# ECG_Main.net
KiCad netlist of a schematic drawn in Altium Designer
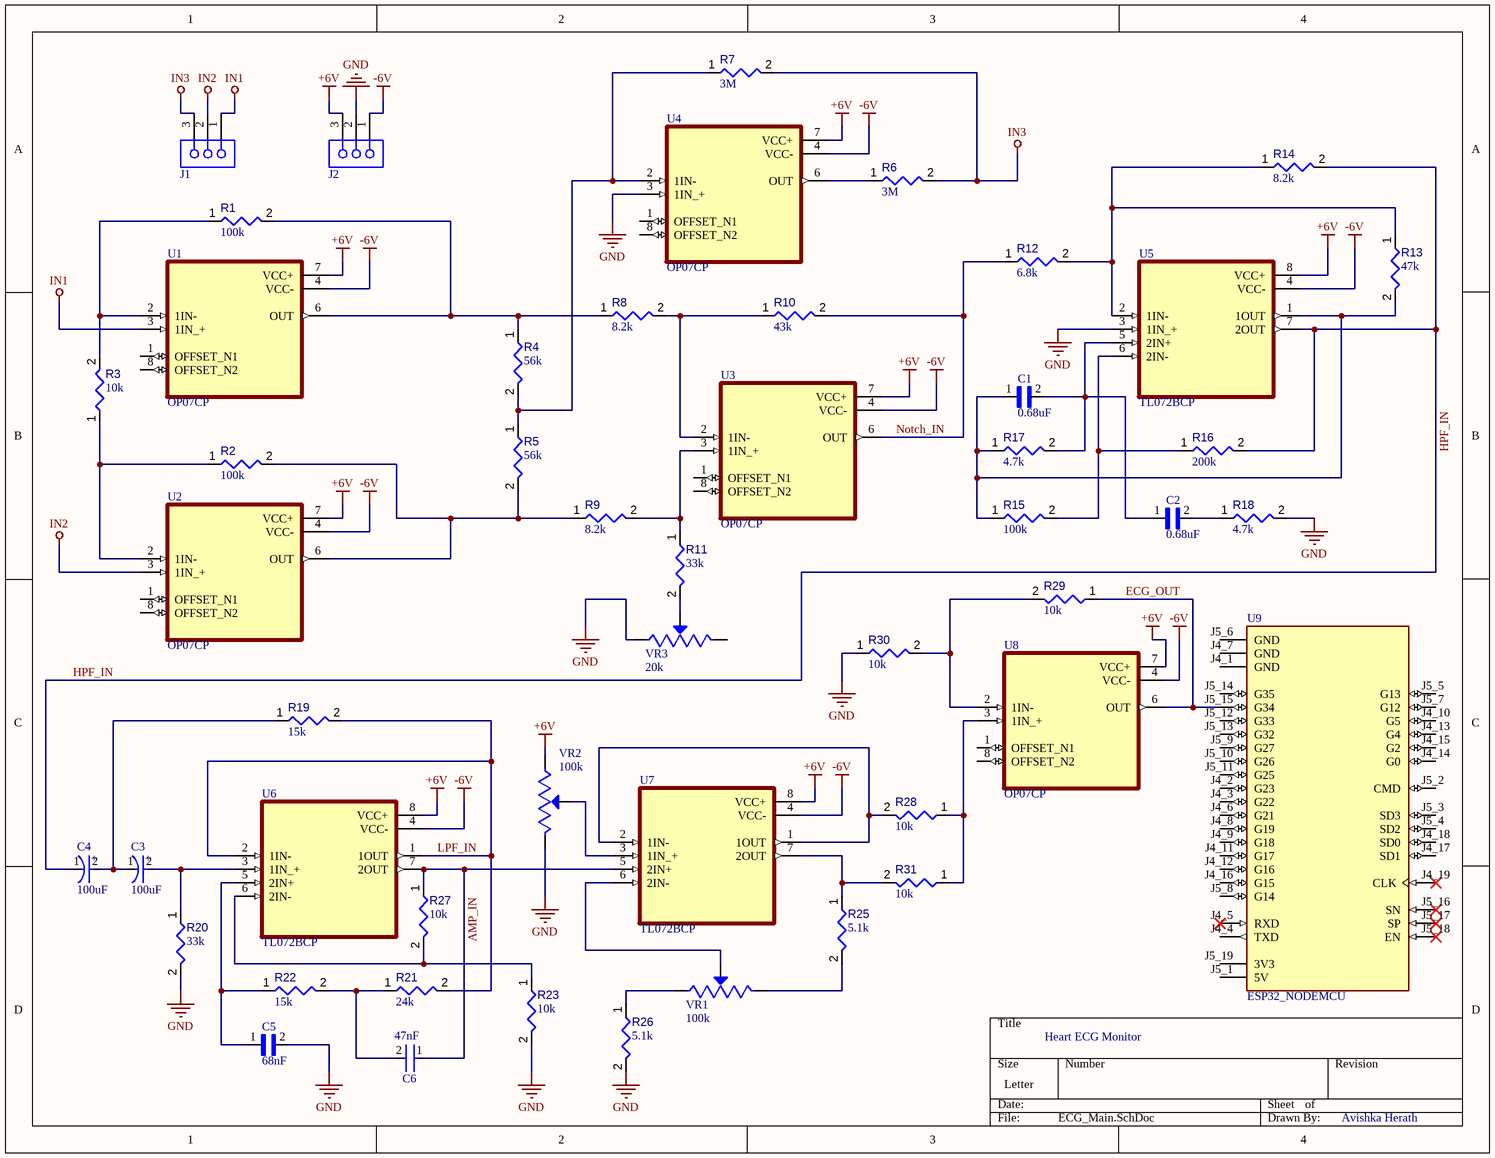
[diagram p0: ECG_Main.SchDoc]

(export (version "E")
  (design (tool "Eeschema 10.0.6"))
  (components
    (comp (ref "C1")
      (value "0.68uF")
      (footprint "CAPRB500W50L550T350H600")
      (fields (field (name "MP") "FA26NP02J472JNU06") (field (name "MF") "{'manufacturer': u'TDK'}"))
      (libsource (lib "SnapEDA_Library") (part "FA26NP02J472JNU06"))
    )
    (comp (ref "C2")
      (value "0.68uF")
      (footprint "CAPRB500W50L550T350H600")
      (fields (field (name "MP") "FA26NP02J472JNU06") (field (name "MF") "{'manufacturer': u'TDK'}"))
      (libsource (lib "SnapEDA_Library") (part "FA26NP02J472JNU06"))
    )
    (comp (ref "C3")
      (value "100uF")
      (footprint "FP-RAD-TH-D_6_3_0_5-L_11-MFG")
      (description "Cap Aluminum Lytic 100uF 25V 20% (6.3 X 11.2mm) Radial 2.5mm 130mA 1000h 105°C Ammo Pack")
      (libsource (lib "University of Moratuwa") (part "203bc49f2ac43e59fd269a8c329ed05"))
    )
    (comp (ref "C4")
      (value "100uF")
      (footprint "FP-RAD-TH-D_6_3_0_5-L_11-MFG")
      (description "Cap Aluminum Lytic 100uF 25V 20% (6.3 X 11.2mm) Radial 2.5mm 130mA 1000h 105°C Ammo Pack")
      (libsource (lib "University of Moratuwa") (part "203bc49f2ac43e59fd269a8c329ed05"))
    )
    (comp (ref "C5")
      (value "68nF")
      (footprint "CAPRR750W60L1030T450H750")
      (fields (field (name "MP") "ECQE2683JF") (field (name "MF") "{'manufacturer': u'Panasonic'}"))
      (libsource (lib "SnapEDA_Library") (part "ECQE2683JF"))
    )
    (comp (ref "C6")
      (value "47nF")
      (footprint "FP-RCE0DB-MFG")
      (description "Cap Ceramic 470pF 50V C0G 5% Radial 2.5mm 125°C Ammo Pack")
      (libsource (lib "University of Moratuwa") (part "b4654b650e69147ec39a6b967a45e02"))
    )
    (comp (ref "J1")
      (value "SIGNAL_IN")
      (footprint "SMTC-SLW-103-01-X-S")
      (fields (field (name "MANUFACTURER") "Samtec") (field (name "PARTNUMBER") "SLW-103-01-G-S"))
      (libsource (lib "Altium Content Vault") (part "SMTC-SLW-103-01-X-S"))
    )
    (comp (ref "J2")
      (value "POWER_IN")
      (footprint "SMTC-SLW-103-01-X-S")
      (fields (field (name "MANUFACTURER") "Samtec") (field (name "PARTNUMBER") "SLW-103-01-G-S"))
      (libsource (lib "Altium Content Vault") (part "SMTC-SLW-103-01-X-S"))
    )
    (comp (ref "R1")
      (value "100k")
      (footprint "RESA60-630X240")
      (description "Axial Resistor, 100 KOhm, +/- 1%, 0.25 W, -55 to 155 degC, 2-Pin THD, RoHS, Bulk")
      (fields (field (name "POWER") "250mW") (field (name "MANUFACTURER") "Yageo"))
      (libsource (lib "University of Moratuwa") (part "RES-2"))
    )
    (comp (ref "R2")
      (value "100k")
      (footprint "RESA60-630X240")
      (description "Axial Resistor, 100 KOhm, +/- 1%, 0.25 W, -55 to 155 degC, 2-Pin THD, RoHS, Bulk")
      (fields (field (name "POWER") "250mW") (field (name "MANUFACTURER") "Yageo"))
      (libsource (lib "University of Moratuwa") (part "RES-2"))
    )
    (comp (ref "R3")
      (value "10k")
      (footprint "RESA60-630X240")
      (description "Axial Resistor, 10 KOhm, +/- 1%, 0.25 W, -55 to 155 degC, 2-Pin THD, RoHS, Bulk")
      (fields (field (name "TOLERANCE") "1%") (field (name "POWER") "250mW"))
      (libsource (lib "University of Moratuwa") (part "RES-2"))
    )
    (comp (ref "R4")
      (value "56k")
      (footprint "RESA60-630X240")
      (description "Axial Resistor, 47.5 KOhm, +/- 1%, 0.25 W, -55 to 155 degC, 2-Pin THD, RoHS, Bulk")
      (fields (field (name "MANUFACTURER") "Yageo") (field (name "TOLERANCE") "1%"))
      (libsource (lib "University of Moratuwa") (part "RES-2"))
    )
    (comp (ref "R5")
      (value "56k")
      (footprint "RESA60-630X240")
      (description "Axial Resistor, 47.5 KOhm, +/- 1%, 0.25 W, -55 to 155 degC, 2-Pin THD, RoHS, Bulk")
      (fields (field (name "MANUFACTURER") "Yageo") (field (name "TOLERANCE") "1%"))
      (libsource (lib "University of Moratuwa") (part "RES-2"))
    )
    (comp (ref "R6")
      (value "3M")
      (footprint "RESA60-630X240")
      (description "Axial Resistor, 1 MOhm, +/- 1%, 250 mW, -55 to 155 degC, 2-Pin THD, RoHS, Bulk")
      (fields (field (name "MANUFACTURER") "Yageo") (field (name "TOLERANCE") "1%"))
      (libsource (lib "University of Moratuwa") (part "RES-2"))
    )
    (comp (ref "R7")
      (value "3M")
      (footprint "RESA60-630X240")
      (description "Axial Resistor, 1 MOhm, +/- 1%, 250 mW, -55 to 155 degC, 2-Pin THD, RoHS, Bulk")
      (fields (field (name "MANUFACTURER") "Yageo") (field (name "TOLERANCE") "1%"))
      (libsource (lib "University of Moratuwa") (part "RES-2"))
    )
    (comp (ref "R8")
      (value "8.2k")
      (footprint "RESA60-630X240")
      (description "Axial Resistor, 4.75 KOhm, +/- 1%, 0.25 W, -55 to 155 degC, 2-Pin THD, RoHS, Bulk")
      (fields (field (name "POWER") "250mW") (field (name "TOLERANCE") "1%"))
      (libsource (lib "University of Moratuwa") (part "RES-2"))
    )
    (comp (ref "R9")
      (value "8.2k")
      (footprint "RESA60-630X240")
      (description "Axial Resistor, 4.75 KOhm, +/- 1%, 0.25 W, -55 to 155 degC, 2-Pin THD, RoHS, Bulk")
      (fields (field (name "POWER") "250mW") (field (name "TOLERANCE") "1%"))
      (libsource (lib "University of Moratuwa") (part "RES-2"))
    )
    (comp (ref "R10")
      (value "43k")
      (footprint "RESA60-630X240")
      (description "Axial Resistor, 47.5 KOhm, +/- 1%, 0.25 W, -55 to 155 degC, 2-Pin THD, RoHS, Bulk")
      (fields (field (name "MANUFACTURER") "Yageo") (field (name "TOLERANCE") "1%"))
      (libsource (lib "University of Moratuwa") (part "RES-2"))
    )
    (comp (ref "R11")
      (value "33k")
      (footprint "RESA60-630X240")
      (description "Axial Resistor, 47.5 KOhm, +/- 1%, 0.25 W, -55 to 155 degC, 2-Pin THD, RoHS, Bulk")
      (fields (field (name "MANUFACTURER") "Yageo") (field (name "TOLERANCE") "1%"))
      (libsource (lib "University of Moratuwa") (part "RES-2"))
    )
    (comp (ref "R12")
      (value "6.8k")
      (footprint "RESA60-630X240")
      (description "Axial Resistor, 47.5 Ohm, +/- 1%, 0.25 W, -55 to 155 degC, 2-Pin THD, RoHS, Bulk")
      (fields (field (name "MANUFACTURER") "Yageo") (field (name "TOLERANCE") "1%"))
      (libsource (lib "University of Moratuwa") (part "RES-2"))
    )
    (comp (ref "R13")
      (value "47k")
      (footprint "RESA60-630X240")
      (description "Axial Resistor, 47.5 Ohm, +/- 1%, 0.25 W, -55 to 155 degC, 2-Pin THD, RoHS, Bulk")
      (fields (field (name "MANUFACTURER") "Yageo") (field (name "TOLERANCE") "1%"))
      (libsource (lib "University of Moratuwa") (part "RES-2"))
    )
    (comp (ref "R14")
      (value "8.2k")
      (footprint "RESA60-630X240")
      (description "Axial Resistor, 47.5 Ohm, +/- 1%, 0.25 W, -55 to 155 degC, 2-Pin THD, RoHS, Bulk")
      (fields (field (name "MANUFACTURER") "Yageo") (field (name "TOLERANCE") "1%"))
      (libsource (lib "University of Moratuwa") (part "RES-2"))
    )
    (comp (ref "R15")
      (value "100k")
      (footprint "RESA60-630X240")
      (description "Axial Resistor, 47.5 Ohm, +/- 1%, 0.25 W, -55 to 155 degC, 2-Pin THD, RoHS, Bulk")
      (fields (field (name "MANUFACTURER") "Yageo") (field (name "TOLERANCE") "1%"))
      (libsource (lib "University of Moratuwa") (part "RES-2"))
    )
    (comp (ref "R16")
      (value "200k")
      (footprint "RESA60-630X240")
      (description "Axial Resistor, 47.5 Ohm, +/- 1%, 0.25 W, -55 to 155 degC, 2-Pin THD, RoHS, Bulk")
      (fields (field (name "MANUFACTURER") "Yageo") (field (name "TOLERANCE") "1%"))
      (libsource (lib "University of Moratuwa") (part "RES-2"))
    )
    (comp (ref "R17")
      (value "4.7k")
      (footprint "RESA60-630X240")
      (description "Axial Resistor, 47.5 Ohm, +/- 1%, 0.25 W, -55 to 155 degC, 2-Pin THD, RoHS, Bulk")
      (fields (field (name "MANUFACTURER") "Yageo") (field (name "TOLERANCE") "1%"))
      (libsource (lib "University of Moratuwa") (part "RES-2"))
    )
    (comp (ref "R18")
      (value "4.7k")
      (footprint "RESA60-630X240")
      (description "Axial Resistor, 47.5 Ohm, +/- 1%, 0.25 W, -55 to 155 degC, 2-Pin THD, RoHS, Bulk")
      (fields (field (name "MANUFACTURER") "Yageo") (field (name "TOLERANCE") "1%"))
      (libsource (lib "University of Moratuwa") (part "RES-2"))
    )
    (comp (ref "R19")
      (value "15k")
      (footprint "RESA60-630X240")
      (description "Axial Resistor, 47.5 Ohm, +/- 1%, 0.25 W, -55 to 155 degC, 2-Pin THD, RoHS, Bulk")
      (fields (field (name "MANUFACTURER") "Yageo") (field (name "TOLERANCE") "1%"))
      (libsource (lib "University of Moratuwa") (part "RES-2"))
    )
    (comp (ref "R20")
      (value "33k")
      (footprint "RESA60-630X240")
      (description "Axial Resistor, 47.5 Ohm, +/- 1%, 0.25 W, -55 to 155 degC, 2-Pin THD, RoHS, Bulk")
      (fields (field (name "MANUFACTURER") "Yageo") (field (name "TOLERANCE") "1%"))
      (libsource (lib "University of Moratuwa") (part "RES-2"))
    )
    (comp (ref "R21")
      (value "24k")
      (footprint "RESA60-630X240")
      (description "Axial Resistor, 10 KOhm, +/- 1%, 0.25 W, -55 to 155 degC, 2-Pin THD, RoHS, Bulk")
      (fields (field (name "TOLERANCE") "1%") (field (name "POWER") "250mW"))
      (libsource (lib "University of Moratuwa") (part "RES-2"))
    )
    (comp (ref "R22")
      (value "15k")
      (footprint "RESA60-630X240")
      (description "Axial Resistor, 10 KOhm, +/- 1%, 0.25 W, -55 to 155 degC, 2-Pin THD, RoHS, Bulk")
      (fields (field (name "TOLERANCE") "1%") (field (name "POWER") "250mW"))
      (libsource (lib "University of Moratuwa") (part "RES-2"))
    )
    (comp (ref "R23")
      (value "10k")
      (footprint "RESA60-630X240")
      (description "Axial Resistor, 10 KOhm, +/- 1%, 0.25 W, -55 to 155 degC, 2-Pin THD, RoHS, Bulk")
      (fields (field (name "TOLERANCE") "1%") (field (name "POWER") "250mW"))
      (libsource (lib "University of Moratuwa") (part "RES-2"))
    )
    (comp (ref "R25")
      (value "5.1k")
      (footprint "RESA60-630X240")
      (description "Axial Resistor, 10 KOhm, +/- 1%, 0.25 W, -55 to 155 degC, 2-Pin THD, RoHS, Bulk")
      (fields (field (name "TOLERANCE") "1%") (field (name "POWER") "250mW"))
      (libsource (lib "University of Moratuwa") (part "RES-2"))
    )
    (comp (ref "R26")
      (value "5.1k")
      (footprint "RESA60-630X240")
      (description "Axial Resistor, 10 KOhm, +/- 1%, 0.25 W, -55 to 155 degC, 2-Pin THD, RoHS, Bulk")
      (fields (field (name "TOLERANCE") "1%") (field (name "POWER") "250mW"))
      (libsource (lib "University of Moratuwa") (part "RES-2"))
    )
    (comp (ref "R27")
      (value "10k")
      (footprint "RESA60-630X240")
      (description "Axial Resistor, 10 KOhm, +/- 1%, 0.25 W, -55 to 155 degC, 2-Pin THD, RoHS, Bulk")
      (fields (field (name "TOLERANCE") "1%") (field (name "POWER") "250mW"))
      (libsource (lib "University of Moratuwa") (part "RES-2"))
    )
    (comp (ref "R28")
      (value "10k")
      (footprint "RESA60-630X240")
      (description "Axial Resistor, 10 KOhm, +/- 1%, 0.25 W, -55 to 155 degC, 2-Pin THD, RoHS, Bulk")
      (fields (field (name "TOLERANCE") "1%") (field (name "POWER") "250mW"))
      (libsource (lib "University of Moratuwa") (part "RES-2"))
    )
    (comp (ref "R29")
      (value "10k")
      (footprint "RESA60-630X240")
      (description "Axial Resistor, 10 KOhm, +/- 1%, 0.25 W, -55 to 155 degC, 2-Pin THD, RoHS, Bulk")
      (fields (field (name "TOLERANCE") "1%") (field (name "POWER") "250mW"))
      (libsource (lib "University of Moratuwa") (part "RES-2"))
    )
    (comp (ref "R30")
      (value "10k")
      (footprint "RESA60-630X240")
      (description "Axial Resistor, 10 KOhm, +/- 1%, 0.25 W, -55 to 155 degC, 2-Pin THD, RoHS, Bulk")
      (fields (field (name "TOLERANCE") "1%") (field (name "POWER") "250mW"))
      (libsource (lib "University of Moratuwa") (part "RES-2"))
    )
    (comp (ref "R31")
      (value "10k")
      (footprint "RESA60-630X240")
      (description "Axial Resistor, 10 KOhm, +/- 1%, 0.25 W, -55 to 155 degC, 2-Pin THD, RoHS, Bulk")
      (fields (field (name "TOLERANCE") "1%") (field (name "POWER") "250mW"))
      (libsource (lib "University of Moratuwa") (part "RES-2"))
    )
    (comp (ref "U1")
      (value "OP07CP")
      (footprint "DIP794W45P254L959H508Q8")
      (fields (field (name "MF") "{'manufacturer': u'Texas Instruments'}"))
      (libsource (lib "SnapEDA_Library") (part "OP07CP"))
    )
    (comp (ref "U2")
      (value "OP07CP")
      (footprint "DIP794W45P254L959H508Q8")
      (fields (field (name "MF") "{'manufacturer': u'Texas Instruments'}"))
      (libsource (lib "SnapEDA_Library") (part "OP07CP"))
    )
    (comp (ref "U3")
      (value "OP07CP")
      (footprint "DIP794W45P254L959H508Q8")
      (fields (field (name "MF") "{'manufacturer': u'Texas Instruments'}"))
      (libsource (lib "SnapEDA_Library") (part "OP07CP"))
    )
    (comp (ref "U4")
      (value "OP07CP")
      (footprint "DIP794W45P254L959H508Q8")
      (fields (field (name "MF") "{'manufacturer': u'Texas Instruments'}"))
      (libsource (lib "SnapEDA_Library") (part "OP07CP"))
    )
    (comp (ref "U5")
      (value "TL072BCP")
      (footprint "DIP794W45P254L959H508Q8")
      (description "Dual low-noise JFET-input low offset operational amplifier 8-PDIP 0 to 70")
      (fields (field (name "MF") "Texas Instruments"))
      (libsource (lib "University of Moratuwa") (part "TL072BCP"))
    )
    (comp (ref "U6")
      (value "TL072BCP")
      (footprint "DIP794W45P254L959H508Q8")
      (description "Dual low-noise JFET-input low offset operational amplifier 8-PDIP 0 to 70")
      (fields (field (name "MF") "Texas Instruments"))
      (libsource (lib "University of Moratuwa") (part "TL072BCP"))
    )
    (comp (ref "U7")
      (value "TL072BCP")
      (footprint "DIP794W45P254L959H508Q8")
      (description "Dual low-noise JFET-input low offset operational amplifier 8-PDIP 0 to 70")
      (fields (field (name "MF") "Texas Instruments"))
      (libsource (lib "University of Moratuwa") (part "TL072BCP"))
    )
    (comp (ref "U8")
      (value "OP07CP")
      (footprint "DIP794W45P254L959H508Q8")
      (fields (field (name "MF") "{'manufacturer': u'Texas Instruments'}"))
      (libsource (lib "SnapEDA_Library") (part "OP07CP"))
    )
    (comp (ref "U9")
      (value "ESP32_NODEMCU")
      (footprint "MODULE_ESP32_NODEMCU")
      (fields (field (name "MF") "{'manufacturer': u'Espressif Systems'}"))
      (libsource (lib "SnapEDA_Library") (part "ESP32_NODEMCU"))
    )
    (comp (ref "VR1")
      (value "100k")
      (footprint "TRIM_3296W-OT1-103")
      (fields (field (name "MP") "3296W-OT1-103") (field (name "MF") "{'manufacturer': u'Bourns'}"))
      (libsource (lib "SnapEDA_Library") (part "3296W-OT1-103"))
    )
    (comp (ref "VR2")
      (value "100k")
      (footprint "TRIM_3296W-OT1-103")
      (fields (field (name "MP") "3296W-OT1-103") (field (name "MF") "{'manufacturer': u'Bourns'}"))
      (libsource (lib "SnapEDA_Library") (part "3296W-OT1-103"))
    )
    (comp (ref "VR3")
      (value "20k")
      (footprint "TRIM_3296W-OT1-103")
      (fields (field (name "MP") "3296W-OT1-103") (field (name "MF") "{'manufacturer': u'Bourns'}"))
      (libsource (lib "SnapEDA_Library") (part "3296W-OT1-103"))
    )
  )
  (nets
    (net (code "1") (name "+6V") (class "Default")
      (node (ref "J2") (pin "3") (pinfunction "3_3") (pintype "passive"))
      (node (ref "U1") (pin "7") (pinfunction "VCC+_7") (pintype "power_in"))
      (node (ref "U2") (pin "7") (pinfunction "VCC+_7") (pintype "power_in"))
      (node (ref "U3") (pin "7") (pinfunction "VCC+_7") (pintype "power_in"))
      (node (ref "U4") (pin "7") (pinfunction "VCC+_7") (pintype "power_in"))
      (node (ref "U5") (pin "8") (pinfunction "VCC+_8") (pintype "power_in"))
      (node (ref "U6") (pin "8") (pinfunction "VCC+_8") (pintype "power_in"))
      (node (ref "U7") (pin "8") (pinfunction "VCC+_8") (pintype "power_in"))
      (node (ref "U8") (pin "7") (pinfunction "VCC+_7") (pintype "power_in"))
      (node (ref "VR2") (pin "3") (pinfunction "CW_3") (pintype "passive"))
    )
    (net (code "2") (name "-6V") (class "Default")
      (node (ref "J2") (pin "1") (pinfunction "1_1") (pintype "passive"))
      (node (ref "U1") (pin "4") (pinfunction "VCC-_4") (pintype "power_in"))
      (node (ref "U2") (pin "4") (pinfunction "VCC-_4") (pintype "power_in"))
      (node (ref "U3") (pin "4") (pinfunction "VCC-_4") (pintype "power_in"))
      (node (ref "U4") (pin "4") (pinfunction "VCC-_4") (pintype "power_in"))
      (node (ref "U5") (pin "4") (pinfunction "VCC-_4") (pintype "power_in"))
      (node (ref "U6") (pin "4") (pinfunction "VCC-_4") (pintype "power_in"))
      (node (ref "U7") (pin "4") (pinfunction "VCC-_4") (pintype "power_in"))
      (node (ref "U8") (pin "4") (pinfunction "VCC-_4") (pintype "power_in"))
    )
    (net (code "3") (name "/AMP_IN") (class "Default")
      (node (ref "C6") (pin "1") (pinfunction "1_1") (pintype "passive"))
      (node (ref "R27") (pin "1") (pinfunction "1_1") (pintype "passive"))
      (node (ref "U6") (pin "7") (pinfunction "2OUT_7") (pintype "output"))
      (node (ref "U7") (pin "5") (pinfunction "2IN+_5") (pintype "input"))
    )
    (net (code "4") (name "/ECG_OUT") (class "Default")
      (node (ref "R29") (pin "1") (pinfunction "1_1") (pintype "passive"))
      (node (ref "U8") (pin "6") (pinfunction "OUT_6") (pintype "output"))
      (node (ref "U9") (pin "J5_15") (pinfunction "G34_J5_15") (pintype "bidirectional"))
    )
    (net (code "5") (name "/HPF_IN") (class "Default")
      (node (ref "C4") (pin "1") (pinfunction "C_1") (pintype "passive"))
      (node (ref "R14") (pin "2") (pinfunction "2_2") (pintype "passive"))
      (node (ref "R16") (pin "2") (pinfunction "2_2") (pintype "passive"))
      (node (ref "U5") (pin "7") (pinfunction "2OUT_7") (pintype "output"))
    )
    (net (code "6") (name "/LPF_IN") (class "Default")
      (node (ref "R19") (pin "2") (pinfunction "2_2") (pintype "passive"))
      (node (ref "R21") (pin "2") (pinfunction "2_2") (pintype "passive"))
      (node (ref "U6") (pin "1") (pinfunction "1OUT_1") (pintype "output"))
      (node (ref "U6") (pin "2") (pinfunction "1IN-_2") (pintype "input"))
    )
    (net (code "7") (name "/Notch_IN") (class "Default")
      (node (ref "R10") (pin "2") (pinfunction "2_2") (pintype "passive"))
      (node (ref "R12") (pin "1") (pinfunction "1_1") (pintype "passive"))
      (node (ref "U3") (pin "6") (pinfunction "OUT_6") (pintype "output"))
    )
    (net (code "8") (name "GND") (class "Default")
      (node (ref "C5") (pin "2") (pinfunction "2_2") (pintype "passive"))
      (node (ref "J2") (pin "2") (pinfunction "2_2") (pintype "passive"))
      (node (ref "R18") (pin "2") (pinfunction "2_2") (pintype "passive"))
      (node (ref "R20") (pin "2") (pinfunction "2_2") (pintype "passive"))
      (node (ref "R23") (pin "2") (pinfunction "2_2") (pintype "passive"))
      (node (ref "R26") (pin "2") (pinfunction "2_2") (pintype "passive"))
      (node (ref "R30") (pin "1") (pinfunction "1_1") (pintype "passive"))
      (node (ref "U4") (pin "3") (pinfunction "1IN_+_3") (pintype "input"))
      (node (ref "U5") (pin "3") (pinfunction "1IN_+_3") (pintype "input"))
      (node (ref "VR2") (pin "1") (pinfunction "CCW_1") (pintype "passive"))
      (node (ref "VR3") (pin "1") (pinfunction "CCW_1") (pintype "passive"))
    )
    (net (code "9") (name "IN1") (class "Default")
      (node (ref "J1") (pin "1") (pinfunction "1_1") (pintype "passive"))
      (node (ref "U1") (pin "3") (pinfunction "1IN_+_3") (pintype "input"))
    )
    (net (code "10") (name "IN2") (class "Default")
      (node (ref "J1") (pin "2") (pinfunction "2_2") (pintype "passive"))
      (node (ref "U2") (pin "3") (pinfunction "1IN_+_3") (pintype "input"))
    )
    (net (code "11") (name "IN3") (class "Default")
      (node (ref "J1") (pin "3") (pinfunction "3_3") (pintype "passive"))
      (node (ref "R6") (pin "2") (pinfunction "2_2") (pintype "passive"))
      (node (ref "R7") (pin "2") (pinfunction "2_2") (pintype "passive"))
    )
    (net (code "12") (name "Net-(C2-Pad2)") (class "Default")
      (node (ref "C2") (pin "2") (pinfunction "2_2") (pintype "passive"))
      (node (ref "R18") (pin "1") (pinfunction "1_1") (pintype "passive"))
    )
    (net (code "13") (name "Net-(C3-A)") (class "Default")
      (node (ref "C3") (pin "2") (pinfunction "A_2") (pintype "passive"))
      (node (ref "R20") (pin "1") (pinfunction "1_1") (pintype "passive"))
      (node (ref "U6") (pin "3") (pinfunction "1IN_+_3") (pintype "input"))
    )
    (net (code "14") (name "Net-(C3-C)") (class "Default")
      (node (ref "C3") (pin "1") (pinfunction "C_1") (pintype "passive"))
      (node (ref "C4") (pin "2") (pinfunction "A_2") (pintype "passive"))
      (node (ref "R19") (pin "1") (pinfunction "1_1") (pintype "passive"))
    )
    (net (code "15") (name "Net-(C6-Pad2)") (class "Default")
      (node (ref "C6") (pin "2") (pinfunction "2_2") (pintype "passive"))
      (node (ref "R21") (pin "1") (pinfunction "1_1") (pintype "passive"))
      (node (ref "R22") (pin "2") (pinfunction "2_2") (pintype "passive"))
    )
    (net (code "16") (name "Net-(U1-1IN-)") (class "Default")
      (node (ref "R1") (pin "1") (pinfunction "1_1") (pintype "passive"))
      (node (ref "R3") (pin "2") (pinfunction "2_2") (pintype "passive"))
      (node (ref "U1") (pin "2") (pinfunction "1IN-_2") (pintype "input"))
    )
    (net (code "17") (name "Net-(U1-OUT)") (class "Default")
      (node (ref "R1") (pin "2") (pinfunction "2_2") (pintype "passive"))
      (node (ref "R4") (pin "1") (pinfunction "1_1") (pintype "passive"))
      (node (ref "R8") (pin "1") (pinfunction "1_1") (pintype "passive"))
      (node (ref "U1") (pin "6") (pinfunction "OUT_6") (pintype "output"))
    )
    (net (code "18") (name "Net-(U2-1IN-)") (class "Default")
      (node (ref "R2") (pin "1") (pinfunction "1_1") (pintype "passive"))
      (node (ref "R3") (pin "1") (pinfunction "1_1") (pintype "passive"))
      (node (ref "U2") (pin "2") (pinfunction "1IN-_2") (pintype "input"))
    )
    (net (code "19") (name "Net-(U2-OUT)") (class "Default")
      (node (ref "R2") (pin "2") (pinfunction "2_2") (pintype "passive"))
      (node (ref "R5") (pin "2") (pinfunction "2_2") (pintype "passive"))
      (node (ref "R9") (pin "1") (pinfunction "1_1") (pintype "passive"))
      (node (ref "U2") (pin "6") (pinfunction "OUT_6") (pintype "output"))
    )
    (net (code "20") (name "Net-(U3-1IN-)") (class "Default")
      (node (ref "R10") (pin "1") (pinfunction "1_1") (pintype "passive"))
      (node (ref "R8") (pin "2") (pinfunction "2_2") (pintype "passive"))
      (node (ref "U3") (pin "2") (pinfunction "1IN-_2") (pintype "input"))
    )
    (net (code "21") (name "Net-(U3-1IN_+)") (class "Default")
      (node (ref "R11") (pin "1") (pinfunction "1_1") (pintype "passive"))
      (node (ref "R9") (pin "2") (pinfunction "2_2") (pintype "passive"))
      (node (ref "U3") (pin "3") (pinfunction "1IN_+_3") (pintype "input"))
    )
    (net (code "22") (name "Net-(U4-1IN-)") (class "Default")
      (node (ref "R4") (pin "2") (pinfunction "2_2") (pintype "passive"))
      (node (ref "R5") (pin "1") (pinfunction "1_1") (pintype "passive"))
      (node (ref "R7") (pin "1") (pinfunction "1_1") (pintype "passive"))
      (node (ref "U4") (pin "2") (pinfunction "1IN-_2") (pintype "input"))
    )
    (net (code "23") (name "Net-(U4-OUT)") (class "Default")
      (node (ref "R6") (pin "1") (pinfunction "1_1") (pintype "passive"))
      (node (ref "U4") (pin "6") (pinfunction "OUT_6") (pintype "output"))
    )
    (net (code "24") (name "Net-(U5-1IN-)") (class "Default")
      (node (ref "R12") (pin "2") (pinfunction "2_2") (pintype "passive"))
      (node (ref "R13") (pin "1") (pinfunction "1_1") (pintype "passive"))
      (node (ref "R14") (pin "1") (pinfunction "1_1") (pintype "passive"))
      (node (ref "U5") (pin "2") (pinfunction "1IN-_2") (pintype "input"))
    )
    (net (code "25") (name "Net-(U5-1OUT)") (class "Default")
      (node (ref "C1") (pin "1") (pinfunction "1_1") (pintype "passive"))
      (node (ref "R13") (pin "2") (pinfunction "2_2") (pintype "passive"))
      (node (ref "R15") (pin "1") (pinfunction "1_1") (pintype "passive"))
      (node (ref "R17") (pin "1") (pinfunction "1_1") (pintype "passive"))
      (node (ref "U5") (pin "1") (pinfunction "1OUT_1") (pintype "output"))
    )
    (net (code "26") (name "Net-(U5-2IN+)") (class "Default")
      (node (ref "C1") (pin "2") (pinfunction "2_2") (pintype "passive"))
      (node (ref "C2") (pin "1") (pinfunction "1_1") (pintype "passive"))
      (node (ref "R17") (pin "2") (pinfunction "2_2") (pintype "passive"))
      (node (ref "U5") (pin "5") (pinfunction "2IN+_5") (pintype "input"))
    )
    (net (code "27") (name "Net-(U5-2IN-)") (class "Default")
      (node (ref "R15") (pin "2") (pinfunction "2_2") (pintype "passive"))
      (node (ref "R16") (pin "1") (pinfunction "1_1") (pintype "passive"))
      (node (ref "U5") (pin "6") (pinfunction "2IN-_6") (pintype "input"))
    )
    (net (code "28") (name "Net-(U6-2IN+)") (class "Default")
      (node (ref "C5") (pin "1") (pinfunction "1_1") (pintype "passive"))
      (node (ref "R22") (pin "1") (pinfunction "1_1") (pintype "passive"))
      (node (ref "U6") (pin "5") (pinfunction "2IN+_5") (pintype "input"))
    )
    (net (code "29") (name "Net-(U6-2IN-)") (class "Default")
      (node (ref "R23") (pin "1") (pinfunction "1_1") (pintype "passive"))
      (node (ref "R27") (pin "2") (pinfunction "2_2") (pintype "passive"))
      (node (ref "U6") (pin "6") (pinfunction "2IN-_6") (pintype "input"))
    )
    (net (code "30") (name "Net-(U7-1IN-)") (class "Default")
      (node (ref "R28") (pin "2") (pinfunction "2_2") (pintype "passive"))
      (node (ref "U7") (pin "1") (pinfunction "1OUT_1") (pintype "output"))
      (node (ref "U7") (pin "2") (pinfunction "1IN-_2") (pintype "input"))
    )
    (net (code "31") (name "Net-(U7-1IN_+)") (class "Default")
      (node (ref "U7") (pin "3") (pinfunction "1IN_+_3") (pintype "input"))
      (node (ref "VR2") (pin "2") (pinfunction "WIPER_2") (pintype "passive"))
    )
    (net (code "32") (name "Net-(U7-2IN-)") (class "Default")
      (node (ref "U7") (pin "6") (pinfunction "2IN-_6") (pintype "input"))
      (node (ref "VR1") (pin "2") (pinfunction "WIPER_2") (pintype "passive"))
    )
    (net (code "33") (name "Net-(U7-2OUT)") (class "Default")
      (node (ref "R25") (pin "1") (pinfunction "1_1") (pintype "passive"))
      (node (ref "R31") (pin "2") (pinfunction "2_2") (pintype "passive"))
      (node (ref "U7") (pin "7") (pinfunction "2OUT_7") (pintype "output"))
    )
    (net (code "34") (name "Net-(U8-1IN-)") (class "Default")
      (node (ref "R29") (pin "2") (pinfunction "2_2") (pintype "passive"))
      (node (ref "R30") (pin "2") (pinfunction "2_2") (pintype "passive"))
      (node (ref "U8") (pin "2") (pinfunction "1IN-_2") (pintype "input"))
    )
    (net (code "35") (name "Net-(U8-1IN_+)") (class "Default")
      (node (ref "R28") (pin "1") (pinfunction "1_1") (pintype "passive"))
      (node (ref "R31") (pin "1") (pinfunction "1_1") (pintype "passive"))
      (node (ref "U8") (pin "3") (pinfunction "1IN_+_3") (pintype "input"))
    )
    (net (code "36") (name "Net-(VR1-CCW)") (class "Default")
      (node (ref "R26") (pin "1") (pinfunction "1_1") (pintype "passive"))
      (node (ref "VR1") (pin "1") (pinfunction "CCW_1") (pintype "passive"))
    )
    (net (code "37") (name "Net-(VR1-CW)") (class "Default")
      (node (ref "R25") (pin "2") (pinfunction "2_2") (pintype "passive"))
      (node (ref "VR1") (pin "3") (pinfunction "CW_3") (pintype "passive"))
    )
    (net (code "38") (name "Net-(VR3-WIPER)") (class "Default")
      (node (ref "R11") (pin "2") (pinfunction "2_2") (pintype "passive"))
      (node (ref "VR3") (pin "2") (pinfunction "WIPER_2") (pintype "passive"))
    )
    (net (code "39") (name "unconnected-(U1-OFFSET_N1-Pad1)") (class "Default")
      (node (ref "U1") (pin "1") (pinfunction "OFFSET_N1_1") (pintype "bidirectional"))
    )
    (net (code "40") (name "unconnected-(U1-OFFSET_N2-Pad8)") (class "Default")
      (node (ref "U1") (pin "8") (pinfunction "OFFSET_N2_8") (pintype "bidirectional"))
    )
    (net (code "41") (name "unconnected-(U2-OFFSET_N1-Pad1)") (class "Default")
      (node (ref "U2") (pin "1") (pinfunction "OFFSET_N1_1") (pintype "bidirectional"))
    )
    (net (code "42") (name "unconnected-(U2-OFFSET_N2-Pad8)") (class "Default")
      (node (ref "U2") (pin "8") (pinfunction "OFFSET_N2_8") (pintype "bidirectional"))
    )
    (net (code "43") (name "unconnected-(U3-OFFSET_N1-Pad1)") (class "Default")
      (node (ref "U3") (pin "1") (pinfunction "OFFSET_N1_1") (pintype "bidirectional"))
    )
    (net (code "44") (name "unconnected-(U3-OFFSET_N2-Pad8)") (class "Default")
      (node (ref "U3") (pin "8") (pinfunction "OFFSET_N2_8") (pintype "bidirectional"))
    )
    (net (code "45") (name "unconnected-(U4-OFFSET_N1-Pad1)") (class "Default")
      (node (ref "U4") (pin "1") (pinfunction "OFFSET_N1_1") (pintype "bidirectional"))
    )
    (net (code "46") (name "unconnected-(U4-OFFSET_N2-Pad8)") (class "Default")
      (node (ref "U4") (pin "8") (pinfunction "OFFSET_N2_8") (pintype "bidirectional"))
    )
    (net (code "47") (name "unconnected-(U8-OFFSET_N1-Pad1)") (class "Default")
      (node (ref "U8") (pin "1") (pinfunction "OFFSET_N1_1") (pintype "bidirectional"))
    )
    (net (code "48") (name "unconnected-(U8-OFFSET_N2-Pad8)") (class "Default")
      (node (ref "U8") (pin "8") (pinfunction "OFFSET_N2_8") (pintype "bidirectional"))
    )
    (net (code "49") (name "unconnected-(U9-3V3-PadJ5_19)") (class "Default")
      (node (ref "U9") (pin "J5_19") (pinfunction "3V3_J5_19") (pintype "power_in"))
    )
    (net (code "50") (name "unconnected-(U9-5V-PadJ5_1)") (class "Default")
      (node (ref "U9") (pin "J5_1") (pinfunction "5V_J5_1") (pintype "power_in"))
    )
    (net (code "51") (name "unconnected-(U9-CLK-PadJ4_19)") (class "Default")
      (node (ref "U9") (pin "J4_19") (pinfunction "CLK_J4_19") (pintype "input+no_connect"))
    )
    (net (code "52") (name "unconnected-(U9-CMD-PadJ5_2)") (class "Default")
      (node (ref "U9") (pin "J5_2") (pinfunction "CMD_J5_2") (pintype "bidirectional"))
    )
    (net (code "53") (name "unconnected-(U9-EN-PadJ5_18)") (class "Default")
      (node (ref "U9") (pin "J5_18") (pinfunction "EN_J5_18") (pintype "input+no_connect"))
    )
    (net (code "54") (name "unconnected-(U9-G0-PadJ4_14)") (class "Default")
      (node (ref "U9") (pin "J4_14") (pinfunction "G0_J4_14") (pintype "bidirectional"))
    )
    (net (code "55") (name "unconnected-(U9-G2-PadJ4_15)") (class "Default")
      (node (ref "U9") (pin "J4_15") (pinfunction "G2_J4_15") (pintype "bidirectional"))
    )
    (net (code "56") (name "unconnected-(U9-G4-PadJ4_13)") (class "Default")
      (node (ref "U9") (pin "J4_13") (pinfunction "G4_J4_13") (pintype "bidirectional"))
    )
    (net (code "57") (name "unconnected-(U9-G5-PadJ4_10)") (class "Default")
      (node (ref "U9") (pin "J4_10") (pinfunction "G5_J4_10") (pintype "bidirectional"))
    )
    (net (code "58") (name "unconnected-(U9-G12-PadJ5_7)") (class "Default")
      (node (ref "U9") (pin "J5_7") (pinfunction "G12_J5_7") (pintype "bidirectional"))
    )
    (net (code "59") (name "unconnected-(U9-G13-PadJ5_5)") (class "Default")
      (node (ref "U9") (pin "J5_5") (pinfunction "G13_J5_5") (pintype "bidirectional"))
    )
    (net (code "60") (name "unconnected-(U9-G14-PadJ5_8)") (class "Default")
      (node (ref "U9") (pin "J5_8") (pinfunction "G14_J5_8") (pintype "bidirectional"))
    )
    (net (code "61") (name "unconnected-(U9-G15-PadJ4_16)") (class "Default")
      (node (ref "U9") (pin "J4_16") (pinfunction "G15_J4_16") (pintype "bidirectional"))
    )
    (net (code "62") (name "unconnected-(U9-G16-PadJ4_12)") (class "Default")
      (node (ref "U9") (pin "J4_12") (pinfunction "G16_J4_12") (pintype "bidirectional"))
    )
    (net (code "63") (name "unconnected-(U9-G17-PadJ4_11)") (class "Default")
      (node (ref "U9") (pin "J4_11") (pinfunction "G17_J4_11") (pintype "bidirectional"))
    )
    (net (code "64") (name "unconnected-(U9-G18-PadJ4_9)") (class "Default")
      (node (ref "U9") (pin "J4_9") (pinfunction "G18_J4_9") (pintype "bidirectional"))
    )
    (net (code "65") (name "unconnected-(U9-G19-PadJ4_8)") (class "Default")
      (node (ref "U9") (pin "J4_8") (pinfunction "G19_J4_8") (pintype "bidirectional"))
    )
    (net (code "66") (name "unconnected-(U9-G21-PadJ4_6)") (class "Default")
      (node (ref "U9") (pin "J4_6") (pinfunction "G21_J4_6") (pintype "bidirectional"))
    )
    (net (code "67") (name "unconnected-(U9-G22-PadJ4_3)") (class "Default")
      (node (ref "U9") (pin "J4_3") (pinfunction "G22_J4_3") (pintype "bidirectional"))
    )
    (net (code "68") (name "unconnected-(U9-G23-PadJ4_2)") (class "Default")
      (node (ref "U9") (pin "J4_2") (pinfunction "G23_J4_2") (pintype "bidirectional"))
    )
    (net (code "69") (name "unconnected-(U9-G25-PadJ5_11)") (class "Default")
      (node (ref "U9") (pin "J5_11") (pinfunction "G25_J5_11") (pintype "bidirectional"))
    )
    (net (code "70") (name "unconnected-(U9-G26-PadJ5_10)") (class "Default")
      (node (ref "U9") (pin "J5_10") (pinfunction "G26_J5_10") (pintype "bidirectional"))
    )
    (net (code "71") (name "unconnected-(U9-G27-PadJ5_9)") (class "Default")
      (node (ref "U9") (pin "J5_9") (pinfunction "G27_J5_9") (pintype "bidirectional"))
    )
    (net (code "72") (name "unconnected-(U9-G32-PadJ5_13)") (class "Default")
      (node (ref "U9") (pin "J5_13") (pinfunction "G32_J5_13") (pintype "bidirectional"))
    )
    (net (code "73") (name "unconnected-(U9-G33-PadJ5_12)") (class "Default")
      (node (ref "U9") (pin "J5_12") (pinfunction "G33_J5_12") (pintype "bidirectional"))
    )
    (net (code "74") (name "unconnected-(U9-G35-PadJ5_14)") (class "Default")
      (node (ref "U9") (pin "J5_14") (pinfunction "G35_J5_14") (pintype "bidirectional"))
    )
    (net (code "75") (name "unconnected-(U9-GND-PadJ4_1)") (class "Default")
      (node (ref "U9") (pin "J4_1") (pinfunction "GND_J4_1") (pintype "power_in"))
    )
    (net (code "76") (name "unconnected-(U9-GND-PadJ4_7)") (class "Default")
      (node (ref "U9") (pin "J4_7") (pinfunction "GND_J4_7") (pintype "power_in"))
    )
    (net (code "77") (name "unconnected-(U9-GND-PadJ5_6)") (class "Default")
      (node (ref "U9") (pin "J5_6") (pinfunction "GND_J5_6") (pintype "power_in"))
    )
    (net (code "78") (name "unconnected-(U9-RXD-PadJ4_5)") (class "Default")
      (node (ref "U9") (pin "J4_5") (pinfunction "RXD_J4_5") (pintype "input+no_connect"))
    )
    (net (code "79") (name "unconnected-(U9-SD0-PadJ4_18)") (class "Default")
      (node (ref "U9") (pin "J4_18") (pinfunction "SD0_J4_18") (pintype "bidirectional"))
    )
    (net (code "80") (name "unconnected-(U9-SD1-PadJ4_17)") (class "Default")
      (node (ref "U9") (pin "J4_17") (pinfunction "SD1_J4_17") (pintype "bidirectional"))
    )
    (net (code "81") (name "unconnected-(U9-SD2-PadJ5_4)") (class "Default")
      (node (ref "U9") (pin "J5_4") (pinfunction "SD2_J5_4") (pintype "bidirectional"))
    )
    (net (code "82") (name "unconnected-(U9-SD3-PadJ5_3)") (class "Default")
      (node (ref "U9") (pin "J5_3") (pinfunction "SD3_J5_3") (pintype "bidirectional"))
    )
    (net (code "83") (name "unconnected-(U9-SN-PadJ5_16)") (class "Default")
      (node (ref "U9") (pin "J5_16") (pinfunction "SN_J5_16") (pintype "input+no_connect"))
    )
    (net (code "84") (name "unconnected-(U9-SP-PadJ5_17)") (class "Default")
      (node (ref "U9") (pin "J5_17") (pinfunction "SP_J5_17") (pintype "input+no_connect"))
    )
    (net (code "85") (name "unconnected-(U9-TXD-PadJ4_4)") (class "Default")
      (node (ref "U9") (pin "J4_4") (pinfunction "TXD_J4_4") (pintype "output"))
    )
    (net (code "86") (name "unconnected-(VR3-CW-Pad3)") (class "Default")
      (node (ref "VR3") (pin "3") (pinfunction "CW_3") (pintype "passive"))
    )
  )
)
